# MediaProjectLedBoard.net
KiCad netlist of a schematic drawn in EAGLE
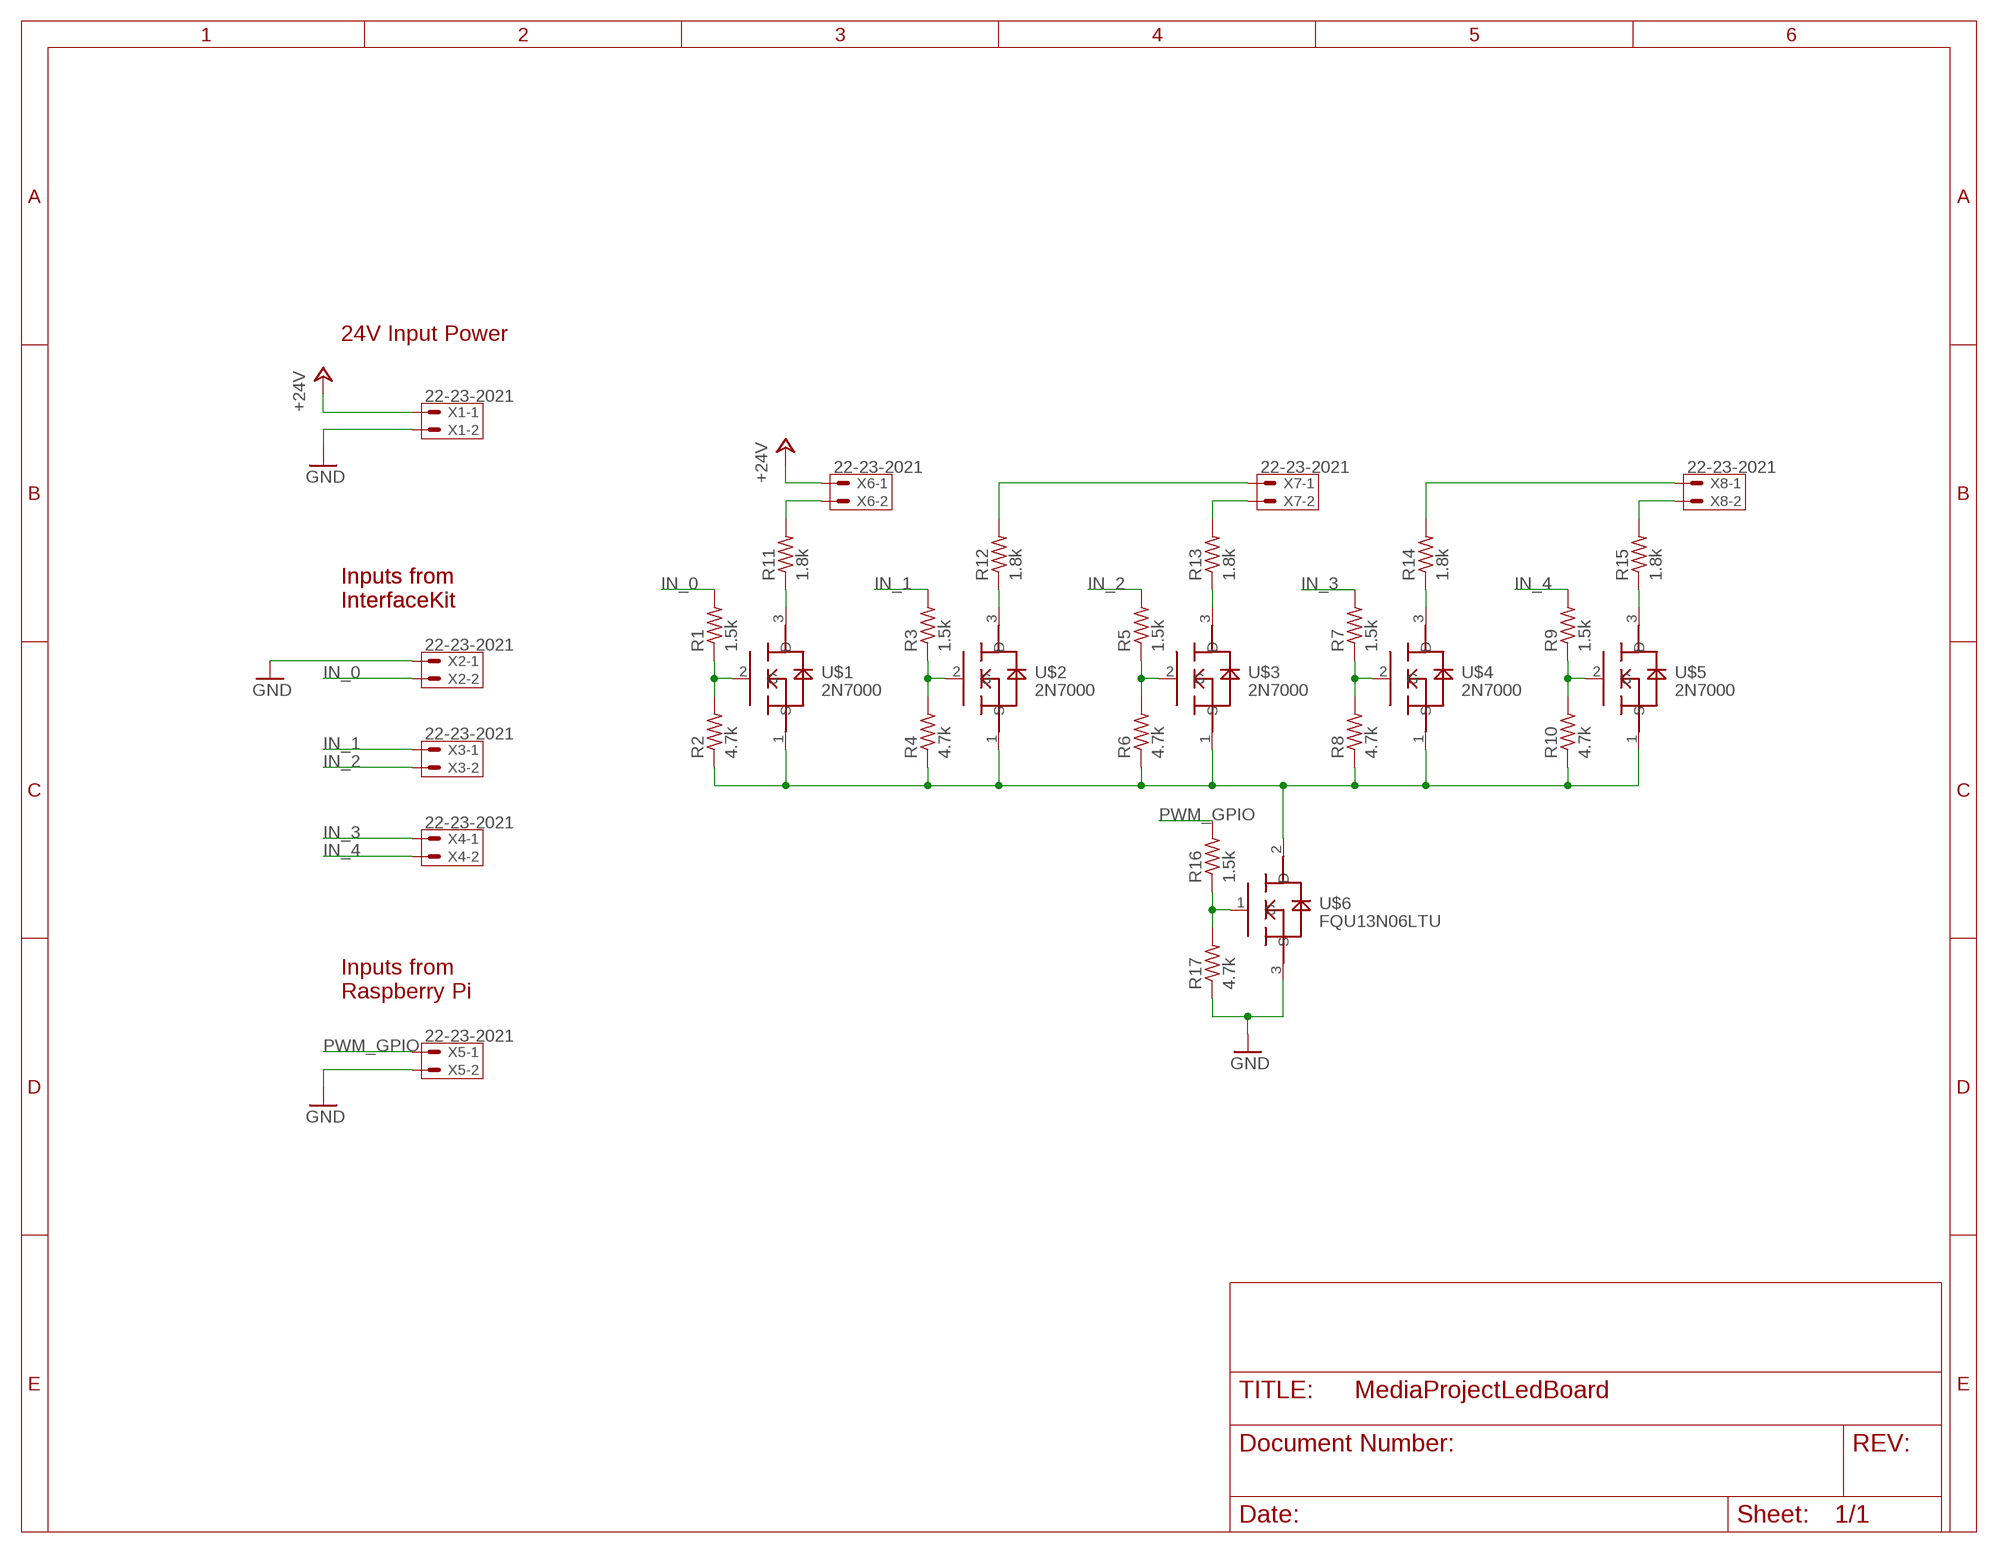
[diagram p0: schematic, sheet 1]

(export (version "E")
  (design (tool "Eeschema 10.0.6"))
  (components
    (comp (ref "R1")
      (value "1.5k")
      (footprint "eagle-import:0309_12")
      (libsource (lib "eagle-import") (part "R-US_0309/12"))
    )
    (comp (ref "R2")
      (value "4.7k")
      (footprint "eagle-import:0309_12")
      (libsource (lib "eagle-import") (part "R-US_0309/12"))
    )
    (comp (ref "R3")
      (value "1.5k")
      (footprint "eagle-import:0309_12")
      (libsource (lib "eagle-import") (part "R-US_0309/12"))
    )
    (comp (ref "R4")
      (value "4.7k")
      (footprint "eagle-import:0309_12")
      (libsource (lib "eagle-import") (part "R-US_0309/12"))
    )
    (comp (ref "R5")
      (value "1.5k")
      (footprint "eagle-import:0309_12")
      (libsource (lib "eagle-import") (part "R-US_0309/12"))
    )
    (comp (ref "R6")
      (value "4.7k")
      (footprint "eagle-import:0309_12")
      (libsource (lib "eagle-import") (part "R-US_0309/12"))
    )
    (comp (ref "R7")
      (value "1.5k")
      (footprint "eagle-import:0309_12")
      (libsource (lib "eagle-import") (part "R-US_0309/12"))
    )
    (comp (ref "R8")
      (value "4.7k")
      (footprint "eagle-import:0309_12")
      (libsource (lib "eagle-import") (part "R-US_0309/12"))
    )
    (comp (ref "R9")
      (value "1.5k")
      (footprint "eagle-import:0309_12")
      (libsource (lib "eagle-import") (part "R-US_0309/12"))
    )
    (comp (ref "R10")
      (value "4.7k")
      (footprint "eagle-import:0309_12")
      (libsource (lib "eagle-import") (part "R-US_0309/12"))
    )
    (comp (ref "R11")
      (value "1.8k")
      (footprint "eagle-import:0309_12")
      (libsource (lib "eagle-import") (part "R-US_0309/12"))
    )
    (comp (ref "R12")
      (value "1.8k")
      (footprint "eagle-import:0309_12")
      (libsource (lib "eagle-import") (part "R-US_0309/12"))
    )
    (comp (ref "R13")
      (value "1.8k")
      (footprint "eagle-import:0309_12")
      (libsource (lib "eagle-import") (part "R-US_0309/12"))
    )
    (comp (ref "R14")
      (value "1.8k")
      (footprint "eagle-import:0309_12")
      (libsource (lib "eagle-import") (part "R-US_0309/12"))
    )
    (comp (ref "R15")
      (value "1.8k")
      (footprint "eagle-import:0309_12")
      (libsource (lib "eagle-import") (part "R-US_0309/12"))
    )
    (comp (ref "R16")
      (value "1.5k")
      (footprint "eagle-import:0309_12")
      (libsource (lib "eagle-import") (part "R-US_0309/12"))
    )
    (comp (ref "R17")
      (value "4.7k")
      (footprint "eagle-import:0309_12")
      (libsource (lib "eagle-import") (part "R-US_0309/12"))
    )
    (comp (ref "U$1")
      (value "2N7000")
      (footprint "eagle-import:TO92-")
      (libsource (lib "eagle-import") (part "2N7000"))
    )
    (comp (ref "U$2")
      (value "2N7000")
      (footprint "eagle-import:TO92-")
      (libsource (lib "eagle-import") (part "2N7000"))
    )
    (comp (ref "U$3")
      (value "2N7000")
      (footprint "eagle-import:TO92-")
      (libsource (lib "eagle-import") (part "2N7000"))
    )
    (comp (ref "U$4")
      (value "2N7000")
      (footprint "eagle-import:TO92-")
      (libsource (lib "eagle-import") (part "2N7000"))
    )
    (comp (ref "U$5")
      (value "2N7000")
      (footprint "eagle-import:TO92-")
      (libsource (lib "eagle-import") (part "2N7000"))
    )
    (comp (ref "U$6")
      (value "FQU13N06LTU")
      (footprint "eagle-import:TO251AA-V")
      (libsource (lib "eagle-import") (part "FQU13N06LTU"))
    )
    (comp (ref "X1")
      (value "22-23-2021")
      (footprint "eagle-import:22-23-2021")
      (fields (field (name "MF") "MOLEX"))
      (libsource (lib "eagle-import") (part "22-23-2021"))
    )
    (comp (ref "X2")
      (value "22-23-2021")
      (footprint "eagle-import:22-23-2021")
      (fields (field (name "MF") "MOLEX"))
      (libsource (lib "eagle-import") (part "22-23-2021"))
    )
    (comp (ref "X3")
      (value "22-23-2021")
      (footprint "eagle-import:22-23-2021")
      (fields (field (name "MF") "MOLEX"))
      (libsource (lib "eagle-import") (part "22-23-2021"))
    )
    (comp (ref "X4")
      (value "22-23-2021")
      (footprint "eagle-import:22-23-2021")
      (fields (field (name "MF") "MOLEX"))
      (libsource (lib "eagle-import") (part "22-23-2021"))
    )
    (comp (ref "X5")
      (value "22-23-2021")
      (footprint "eagle-import:22-23-2021")
      (fields (field (name "MF") "MOLEX"))
      (libsource (lib "eagle-import") (part "22-23-2021"))
    )
    (comp (ref "X6")
      (value "22-23-2021")
      (footprint "eagle-import:22-23-2021")
      (fields (field (name "MF") "MOLEX"))
      (libsource (lib "eagle-import") (part "22-23-2021"))
    )
    (comp (ref "X7")
      (value "22-23-2021")
      (footprint "eagle-import:22-23-2021")
      (fields (field (name "MF") "MOLEX"))
      (libsource (lib "eagle-import") (part "22-23-2021"))
    )
    (comp (ref "X8")
      (value "22-23-2021")
      (footprint "eagle-import:22-23-2021")
      (fields (field (name "MF") "MOLEX"))
      (libsource (lib "eagle-import") (part "22-23-2021"))
    )
  )
  (nets
    (net (code "1") (name "+24V") (class "Default")
      (node (ref "X1") (pin "1") (pinfunction "S_1") (pintype "passive"))
      (node (ref "X6") (pin "1") (pinfunction "S_1") (pintype "passive"))
    )
    (net (code "2") (name "/IN_0") (class "Default")
      (node (ref "R1") (pin "2") (pinfunction "2_2") (pintype "passive"))
      (node (ref "X2") (pin "2") (pinfunction "S_2") (pintype "passive"))
    )
    (net (code "3") (name "/IN_1") (class "Default")
      (node (ref "R3") (pin "2") (pinfunction "2_2") (pintype "passive"))
      (node (ref "X3") (pin "1") (pinfunction "S_1") (pintype "passive"))
    )
    (net (code "4") (name "/IN_2") (class "Default")
      (node (ref "R5") (pin "2") (pinfunction "2_2") (pintype "passive"))
      (node (ref "X3") (pin "2") (pinfunction "S_2") (pintype "passive"))
    )
    (net (code "5") (name "/IN_3") (class "Default")
      (node (ref "R7") (pin "2") (pinfunction "2_2") (pintype "passive"))
      (node (ref "X4") (pin "1") (pinfunction "S_1") (pintype "passive"))
    )
    (net (code "6") (name "/IN_4") (class "Default")
      (node (ref "R9") (pin "2") (pinfunction "2_2") (pintype "passive"))
      (node (ref "X4") (pin "2") (pinfunction "S_2") (pintype "passive"))
    )
    (net (code "7") (name "/PWM_GPIO") (class "Default")
      (node (ref "R16") (pin "2") (pinfunction "2_2") (pintype "passive"))
      (node (ref "X5") (pin "1") (pinfunction "S_1") (pintype "passive"))
    )
    (net (code "8") (name "GND") (class "Default")
      (node (ref "R17") (pin "1") (pinfunction "1_1") (pintype "passive"))
      (node (ref "U$6") (pin "3") (pinfunction "S_3") (pintype "bidirectional"))
      (node (ref "X1") (pin "2") (pinfunction "S_2") (pintype "passive"))
      (node (ref "X2") (pin "1") (pinfunction "S_1") (pintype "passive"))
      (node (ref "X5") (pin "2") (pinfunction "S_2") (pintype "passive"))
    )
    (net (code "9") (name "Net-(U$1-D)") (class "Default")
      (node (ref "R11") (pin "1") (pinfunction "1_1") (pintype "passive"))
      (node (ref "U$1") (pin "3") (pinfunction "D_3") (pintype "bidirectional"))
    )
    (net (code "10") (name "Net-(U$1-G)") (class "Default")
      (node (ref "R1") (pin "1") (pinfunction "1_1") (pintype "passive"))
      (node (ref "R2") (pin "2") (pinfunction "2_2") (pintype "passive"))
      (node (ref "U$1") (pin "2") (pinfunction "G_2") (pintype "bidirectional"))
    )
    (net (code "11") (name "Net-(U$1-S)") (class "Default")
      (node (ref "R10") (pin "1") (pinfunction "1_1") (pintype "passive"))
      (node (ref "R2") (pin "1") (pinfunction "1_1") (pintype "passive"))
      (node (ref "R4") (pin "1") (pinfunction "1_1") (pintype "passive"))
      (node (ref "R6") (pin "1") (pinfunction "1_1") (pintype "passive"))
      (node (ref "R8") (pin "1") (pinfunction "1_1") (pintype "passive"))
      (node (ref "U$1") (pin "1") (pinfunction "S_1") (pintype "bidirectional"))
      (node (ref "U$2") (pin "1") (pinfunction "S_1") (pintype "bidirectional"))
      (node (ref "U$3") (pin "1") (pinfunction "S_1") (pintype "bidirectional"))
      (node (ref "U$4") (pin "1") (pinfunction "S_1") (pintype "bidirectional"))
      (node (ref "U$5") (pin "1") (pinfunction "S_1") (pintype "bidirectional"))
      (node (ref "U$6") (pin "2") (pinfunction "D_2") (pintype "bidirectional"))
    )
    (net (code "12") (name "Net-(U$2-D)") (class "Default")
      (node (ref "R12") (pin "1") (pinfunction "1_1") (pintype "passive"))
      (node (ref "U$2") (pin "3") (pinfunction "D_3") (pintype "bidirectional"))
    )
    (net (code "13") (name "Net-(U$2-G)") (class "Default")
      (node (ref "R3") (pin "1") (pinfunction "1_1") (pintype "passive"))
      (node (ref "R4") (pin "2") (pinfunction "2_2") (pintype "passive"))
      (node (ref "U$2") (pin "2") (pinfunction "G_2") (pintype "bidirectional"))
    )
    (net (code "14") (name "Net-(U$3-D)") (class "Default")
      (node (ref "R13") (pin "1") (pinfunction "1_1") (pintype "passive"))
      (node (ref "U$3") (pin "3") (pinfunction "D_3") (pintype "bidirectional"))
    )
    (net (code "15") (name "Net-(U$3-G)") (class "Default")
      (node (ref "R5") (pin "1") (pinfunction "1_1") (pintype "passive"))
      (node (ref "R6") (pin "2") (pinfunction "2_2") (pintype "passive"))
      (node (ref "U$3") (pin "2") (pinfunction "G_2") (pintype "bidirectional"))
    )
    (net (code "16") (name "Net-(U$4-D)") (class "Default")
      (node (ref "R14") (pin "1") (pinfunction "1_1") (pintype "passive"))
      (node (ref "U$4") (pin "3") (pinfunction "D_3") (pintype "bidirectional"))
    )
    (net (code "17") (name "Net-(U$4-G)") (class "Default")
      (node (ref "R7") (pin "1") (pinfunction "1_1") (pintype "passive"))
      (node (ref "R8") (pin "2") (pinfunction "2_2") (pintype "passive"))
      (node (ref "U$4") (pin "2") (pinfunction "G_2") (pintype "bidirectional"))
    )
    (net (code "18") (name "Net-(U$5-D)") (class "Default")
      (node (ref "R15") (pin "1") (pinfunction "1_1") (pintype "passive"))
      (node (ref "U$5") (pin "3") (pinfunction "D_3") (pintype "bidirectional"))
    )
    (net (code "19") (name "Net-(U$5-G)") (class "Default")
      (node (ref "R10") (pin "2") (pinfunction "2_2") (pintype "passive"))
      (node (ref "R9") (pin "1") (pinfunction "1_1") (pintype "passive"))
      (node (ref "U$5") (pin "2") (pinfunction "G_2") (pintype "bidirectional"))
    )
    (net (code "20") (name "Net-(U$6-G)") (class "Default")
      (node (ref "R16") (pin "1") (pinfunction "1_1") (pintype "passive"))
      (node (ref "R17") (pin "2") (pinfunction "2_2") (pintype "passive"))
      (node (ref "U$6") (pin "1") (pinfunction "G_1") (pintype "bidirectional"))
    )
    (net (code "21") (name "Net-(X6B-S)") (class "Default")
      (node (ref "R11") (pin "2") (pinfunction "2_2") (pintype "passive"))
      (node (ref "X6") (pin "2") (pinfunction "S_2") (pintype "passive"))
    )
    (net (code "22") (name "Net-(X7A-S)") (class "Default")
      (node (ref "R12") (pin "2") (pinfunction "2_2") (pintype "passive"))
      (node (ref "X7") (pin "1") (pinfunction "S_1") (pintype "passive"))
    )
    (net (code "23") (name "Net-(X7B-S)") (class "Default")
      (node (ref "R13") (pin "2") (pinfunction "2_2") (pintype "passive"))
      (node (ref "X7") (pin "2") (pinfunction "S_2") (pintype "passive"))
    )
    (net (code "24") (name "Net-(X8A-S)") (class "Default")
      (node (ref "R14") (pin "2") (pinfunction "2_2") (pintype "passive"))
      (node (ref "X8") (pin "1") (pinfunction "S_1") (pintype "passive"))
    )
    (net (code "25") (name "Net-(X8B-S)") (class "Default")
      (node (ref "R15") (pin "2") (pinfunction "2_2") (pintype "passive"))
      (node (ref "X8") (pin "2") (pinfunction "S_2") (pintype "passive"))
    )
  )
)
